# powerboost.net
KiCad netlist of a schematic drawn in EAGLE
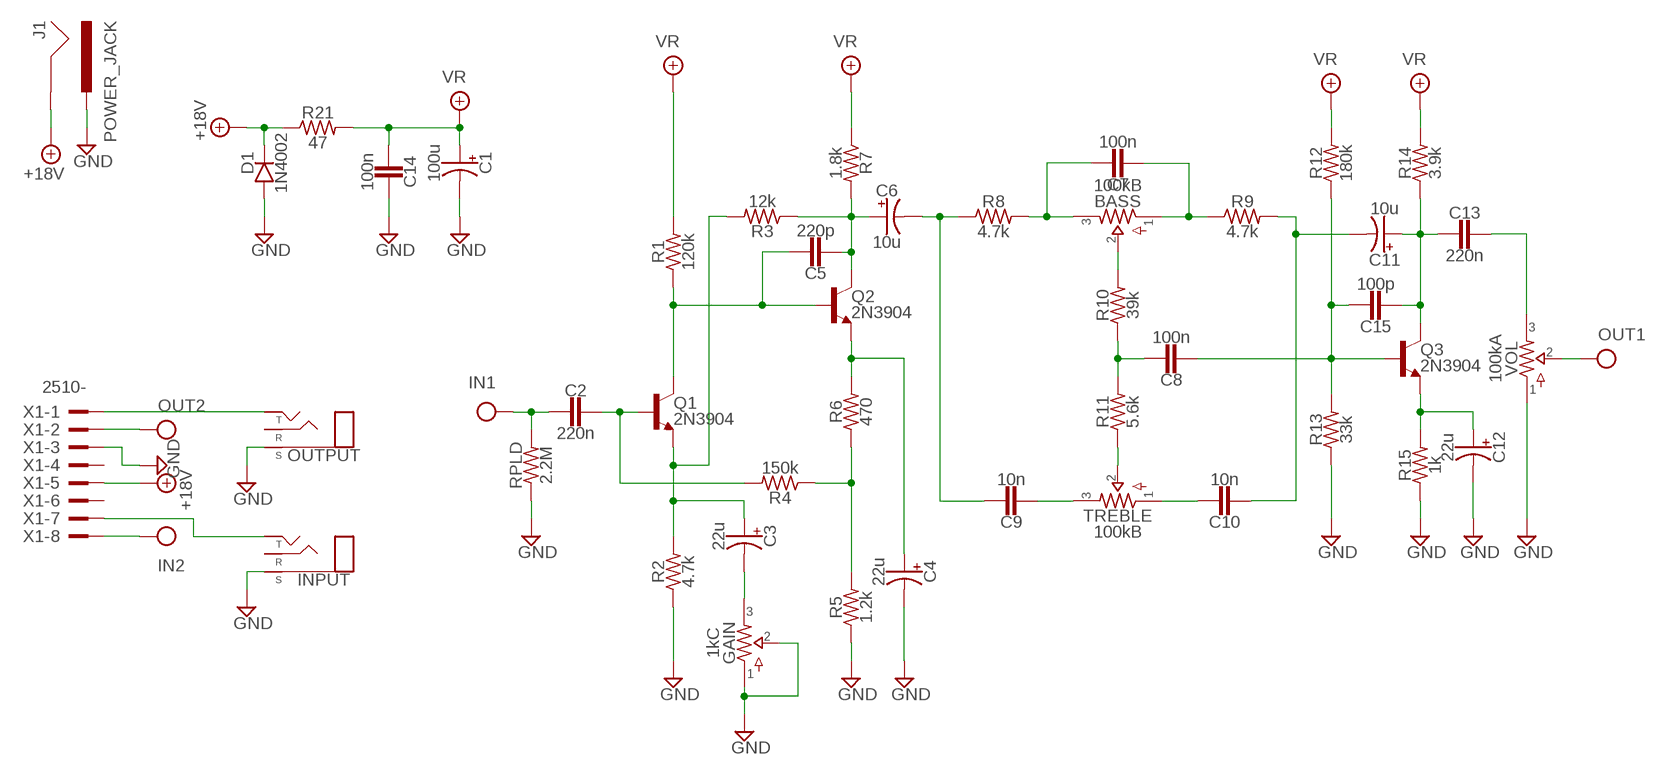
[diagram p0: schematic, sheet 1]

(export (version "E")
  (design (tool "Eeschema 10.0.6"))
  (components
    (comp (ref "BASS")
      (value "100kB")
      (footprint "eagle-import:16MM")
      (libsource (lib "eagle-import") (part "POTS16MM"))
    )
    (comp (ref "C1")
      (value "100u")
      (footprint "eagle-import:063_025")
      (libsource (lib "eagle-import") (part "0631"))
    )
    (comp (ref "C2")
      (value "220n")
      (footprint "eagle-import:BOX_SMALL")
      (libsource (lib "eagle-import") (part "CER/FILMBOX.1"))
    )
    (comp (ref "C3")
      (value "22u")
      (footprint "eagle-import:050_020")
      (libsource (lib "eagle-import") (part "0500"))
    )
    (comp (ref "C4")
      (value "22u")
      (footprint "eagle-import:050_020")
      (libsource (lib "eagle-import") (part "0500"))
    )
    (comp (ref "C5")
      (value "220p")
      (footprint "eagle-import:050X030_025_2")
      (libsource (lib "eagle-import") (part "CER/FILM2"))
    )
    (comp (ref "C6")
      (value "10u")
      (footprint "eagle-import:050_020_1")
      (libsource (lib "eagle-import") (part "0501"))
    )
    (comp (ref "C7")
      (value "100n")
      (footprint "eagle-import:BOX_SMALL")
      (libsource (lib "eagle-import") (part "CER/FILMBOX.1"))
    )
    (comp (ref "C8")
      (value "100n")
      (footprint "eagle-import:BOX_SMALL")
      (libsource (lib "eagle-import") (part "CER/FILMBOX.1"))
    )
    (comp (ref "C9")
      (value "10n")
      (footprint "eagle-import:BOX_SMALL")
      (libsource (lib "eagle-import") (part "CER/FILMBOX.1"))
    )
    (comp (ref "C10")
      (value "10n")
      (footprint "eagle-import:BOX_SMALL")
      (libsource (lib "eagle-import") (part "CER/FILMBOX.1"))
    )
    (comp (ref "C11")
      (value "10u")
      (footprint "eagle-import:050_020_1")
      (libsource (lib "eagle-import") (part "0501"))
    )
    (comp (ref "C12")
      (value "22u")
      (footprint "eagle-import:050_020")
      (libsource (lib "eagle-import") (part "0500"))
    )
    (comp (ref "C13")
      (value "220n")
      (footprint "eagle-import:BOX_SMALL")
      (libsource (lib "eagle-import") (part "CER/FILMBOX.1"))
    )
    (comp (ref "C14")
      (value "100n")
      (footprint "eagle-import:050X030_025_2")
      (libsource (lib "eagle-import") (part "CER/FILM2"))
    )
    (comp (ref "C15")
      (value "100p")
      (footprint "eagle-import:050X030_025_2")
      (libsource (lib "eagle-import") (part "CER/FILM2"))
    )
    (comp (ref "D1")
      (value "1N4002")
      (footprint "eagle-import:DO41-2")
      (libsource (lib "eagle-import") (part "DO41.2"))
    )
    (comp (ref "GAIN")
      (value "1kC")
      (footprint "eagle-import:16MM")
      (libsource (lib "eagle-import") (part "POTS16MM"))
    )
    (comp (ref "INPUT")
      (value "STEREONMJ")
      (footprint "eagle-import:NMJ6HCD2")
      (libsource (lib "eagle-import") (part "STEREONMJ"))
    )
    (comp (ref "J1")
      (value "POWER_JACK")
      (footprint "eagle-import:POWER_JACK_PTH")
      (libsource (lib "eagle-import") (part "POWER_JACK"))
    )
    (comp (ref "OUTPUT")
      (value "STEREONMJ")
      (footprint "eagle-import:NMJ6HCD2")
      (libsource (lib "eagle-import") (part "STEREONMJ"))
    )
    (comp (ref "Q1")
      (value "2N3904")
      (footprint "eagle-import:TO92-")
      (libsource (lib "eagle-import") (part "2N3904"))
    )
    (comp (ref "Q2")
      (value "2N3904")
      (footprint "eagle-import:TO92-")
      (libsource (lib "eagle-import") (part "2N3904"))
    )
    (comp (ref "Q3")
      (value "2N3904")
      (footprint "eagle-import:TO92-")
      (libsource (lib "eagle-import") (part "2N3904"))
    )
    (comp (ref "R1")
      (value "120k")
      (footprint "eagle-import:R0207_3")
      (libsource (lib "eagle-import") (part "R_.3B"))
    )
    (comp (ref "R2")
      (value "4.7k")
      (footprint "eagle-import:R0207_3")
      (libsource (lib "eagle-import") (part "R_.3B"))
    )
    (comp (ref "R3")
      (value "12k")
      (footprint "eagle-import:R0207_3")
      (libsource (lib "eagle-import") (part "R_.3B"))
    )
    (comp (ref "R4")
      (value "150k")
      (footprint "eagle-import:R0207_3")
      (libsource (lib "eagle-import") (part "R_.3B"))
    )
    (comp (ref "R5")
      (value "1.2k")
      (footprint "eagle-import:R0207_3")
      (libsource (lib "eagle-import") (part "R_.3B"))
    )
    (comp (ref "R6")
      (value "470")
      (footprint "eagle-import:R0207_3")
      (libsource (lib "eagle-import") (part "R_.3B"))
    )
    (comp (ref "R7")
      (value "1.8k")
      (footprint "eagle-import:R0207_3")
      (libsource (lib "eagle-import") (part "R_.3B"))
    )
    (comp (ref "R8")
      (value "4.7k")
      (footprint "eagle-import:R0207_3")
      (libsource (lib "eagle-import") (part "R_.3B"))
    )
    (comp (ref "R9")
      (value "4.7k")
      (footprint "eagle-import:R0207_3")
      (libsource (lib "eagle-import") (part "R_.3B"))
    )
    (comp (ref "R10")
      (value "39k")
      (footprint "eagle-import:R0207_3")
      (libsource (lib "eagle-import") (part "R_.3B"))
    )
    (comp (ref "R11")
      (value "5.6k")
      (footprint "eagle-import:R0207_3")
      (libsource (lib "eagle-import") (part "R_.3B"))
    )
    (comp (ref "R12")
      (value "180k")
      (footprint "eagle-import:R0207_3")
      (libsource (lib "eagle-import") (part "R_.3B"))
    )
    (comp (ref "R13")
      (value "33k")
      (footprint "eagle-import:R0207_3")
      (libsource (lib "eagle-import") (part "R_.3B"))
    )
    (comp (ref "R14")
      (value "3.9k")
      (footprint "eagle-import:R0207_3")
      (libsource (lib "eagle-import") (part "R_.3B"))
    )
    (comp (ref "R15")
      (value "1k")
      (footprint "eagle-import:R0207_3")
      (libsource (lib "eagle-import") (part "R_.3B"))
    )
    (comp (ref "R21")
      (value "47")
      (footprint "eagle-import:R0207_3")
      (libsource (lib "eagle-import") (part "R_.3B"))
    )
    (comp (ref "RPLD")
      (value "2.2M")
      (footprint "eagle-import:R0207_3")
      (libsource (lib "eagle-import") (part "R_.3B"))
    )
    (comp (ref "TREBLE")
      (value "100kB")
      (footprint "eagle-import:16MM")
      (libsource (lib "eagle-import") (part "POTS16MM"))
    )
    (comp (ref "VOL")
      (value "100kA")
      (footprint "eagle-import:16MM")
      (libsource (lib "eagle-import") (part "POTS16MM"))
    )
    (comp (ref "X1")
      (value "2510-")
      (footprint "eagle-import:PAK100_2500-10")
      (fields (field (name "MF") "3M") (field (name "MPN") "2510-6002UB"))
      (libsource (lib "eagle-import") (part "2510-"))
    )
  )
  (nets
    (net (code "1") (name "+18V") (class "Default")
      (node (ref "D1") (pin "C") (pinfunction "C_C") (pintype "passive"))
      (node (ref "J1") (pin "GND") (pinfunction "GND_GND") (pintype "bidirectional"))
      (node (ref "R21") (pin "1") (pinfunction "1_1") (pintype "passive"))
      (node (ref "X1") (pin "5") (pinfunction "KL_5") (pintype "passive"))
    )
    (net (code "2") (name "GND") (class "Default")
      (node (ref "C1") (pin "-") (pinfunction "-_-") (pintype "passive"))
      (node (ref "C12") (pin "-") (pinfunction "-_-") (pintype "passive"))
      (node (ref "C14") (pin "1") (pinfunction "1_1") (pintype "passive"))
      (node (ref "C4") (pin "-") (pinfunction "-_-") (pintype "passive"))
      (node (ref "D1") (pin "A") (pinfunction "A_A") (pintype "passive"))
      (node (ref "GAIN") (pin "1") (pinfunction "1_1") (pintype "passive"))
      (node (ref "GAIN") (pin "2") (pinfunction "2_2") (pintype "passive"))
      (node (ref "INPUT") (pin "S") (pinfunction "S_S") (pintype "passive"))
      (node (ref "J1") (pin "PWR") (pinfunction "PWR_PWR") (pintype "bidirectional"))
      (node (ref "OUTPUT") (pin "S") (pinfunction "S_S") (pintype "passive"))
      (node (ref "R13") (pin "1") (pinfunction "1_1") (pintype "passive"))
      (node (ref "R15") (pin "1") (pinfunction "1_1") (pintype "passive"))
      (node (ref "R2") (pin "1") (pinfunction "1_1") (pintype "passive"))
      (node (ref "R5") (pin "1") (pinfunction "1_1") (pintype "passive"))
      (node (ref "RPLD") (pin "1") (pinfunction "1_1") (pintype "passive"))
      (node (ref "VOL") (pin "1") (pinfunction "1_1") (pintype "passive"))
      (node (ref "X1") (pin "3") (pinfunction "KL_3") (pintype "passive"))
    )
    (net (code "3") (name "IN") (class "Default")
      (node (ref "C2") (pin "2") (pinfunction "2_2") (pintype "passive"))
      (node (ref "RPLD") (pin "2") (pinfunction "2_2") (pintype "passive"))
      (node (ref "X1") (pin "8") (pinfunction "KL_8") (pintype "passive"))
    )
    (net (code "4") (name "Net-(BASS-Pad1)") (class "Default")
      (node (ref "BASS") (pin "1") (pinfunction "1_1") (pintype "passive"))
      (node (ref "C7") (pin "2") (pinfunction "2_2") (pintype "passive"))
      (node (ref "R9") (pin "1") (pinfunction "1_1") (pintype "passive"))
    )
    (net (code "5") (name "Net-(BASS-Pad2)") (class "Default")
      (node (ref "BASS") (pin "2") (pinfunction "2_2") (pintype "passive"))
      (node (ref "R10") (pin "2") (pinfunction "2_2") (pintype "passive"))
    )
    (net (code "6") (name "Net-(BASS-Pad3)") (class "Default")
      (node (ref "BASS") (pin "3") (pinfunction "3_3") (pintype "passive"))
      (node (ref "C7") (pin "1") (pinfunction "1_1") (pintype "passive"))
      (node (ref "R8") (pin "2") (pinfunction "2_2") (pintype "passive"))
    )
    (net (code "7") (name "Net-(C3-Pad-)") (class "Default")
      (node (ref "C3") (pin "-") (pinfunction "-_-") (pintype "passive"))
      (node (ref "GAIN") (pin "3") (pinfunction "3_3") (pintype "passive"))
    )
    (net (code "8") (name "Net-(C6-Pad-)") (class "Default")
      (node (ref "C6") (pin "-") (pinfunction "-_-") (pintype "passive"))
      (node (ref "C9") (pin "1") (pinfunction "1_1") (pintype "passive"))
      (node (ref "R8") (pin "1") (pinfunction "1_1") (pintype "passive"))
    )
    (net (code "9") (name "Net-(C8-Pad1)") (class "Default")
      (node (ref "C8") (pin "1") (pinfunction "1_1") (pintype "passive"))
      (node (ref "R10") (pin "1") (pinfunction "1_1") (pintype "passive"))
      (node (ref "R11") (pin "2") (pinfunction "2_2") (pintype "passive"))
    )
    (net (code "10") (name "Net-(C9-Pad2)") (class "Default")
      (node (ref "C9") (pin "2") (pinfunction "2_2") (pintype "passive"))
      (node (ref "TREBLE") (pin "3") (pinfunction "3_3") (pintype "passive"))
    )
    (net (code "11") (name "Net-(C10-Pad1)") (class "Default")
      (node (ref "C10") (pin "1") (pinfunction "1_1") (pintype "passive"))
      (node (ref "TREBLE") (pin "1") (pinfunction "1_1") (pintype "passive"))
    )
    (net (code "12") (name "Net-(C10-Pad2)") (class "Default")
      (node (ref "C10") (pin "2") (pinfunction "2_2") (pintype "passive"))
      (node (ref "C11") (pin "-") (pinfunction "-_-") (pintype "passive"))
      (node (ref "R9") (pin "2") (pinfunction "2_2") (pintype "passive"))
    )
    (net (code "13") (name "Net-(C13-Pad1)") (class "Default")
      (node (ref "C13") (pin "1") (pinfunction "1_1") (pintype "passive"))
      (node (ref "VOL") (pin "3") (pinfunction "3_3") (pintype "passive"))
    )
    (net (code "14") (name "Net-(Q1-B)") (class "Default")
      (node (ref "C2") (pin "1") (pinfunction "1_1") (pintype "passive"))
      (node (ref "Q1") (pin "2") (pinfunction "B_2") (pintype "passive"))
      (node (ref "R4") (pin "2") (pinfunction "2_2") (pintype "passive"))
    )
    (net (code "15") (name "Net-(Q1-C)") (class "Default")
      (node (ref "C5") (pin "1") (pinfunction "1_1") (pintype "passive"))
      (node (ref "Q1") (pin "1") (pinfunction "C_1") (pintype "passive"))
      (node (ref "Q2") (pin "2") (pinfunction "B_2") (pintype "passive"))
      (node (ref "R1") (pin "1") (pinfunction "1_1") (pintype "passive"))
    )
    (net (code "16") (name "Net-(Q1-E)") (class "Default")
      (node (ref "C3") (pin "+") (pinfunction "+_+") (pintype "passive"))
      (node (ref "Q1") (pin "3") (pinfunction "E_3") (pintype "passive"))
      (node (ref "R2") (pin "2") (pinfunction "2_2") (pintype "passive"))
      (node (ref "R3") (pin "2") (pinfunction "2_2") (pintype "passive"))
    )
    (net (code "17") (name "Net-(Q2-C)") (class "Default")
      (node (ref "C5") (pin "2") (pinfunction "2_2") (pintype "passive"))
      (node (ref "C6") (pin "+") (pinfunction "+_+") (pintype "passive"))
      (node (ref "Q2") (pin "1") (pinfunction "C_1") (pintype "passive"))
      (node (ref "R3") (pin "1") (pinfunction "1_1") (pintype "passive"))
      (node (ref "R7") (pin "2") (pinfunction "2_2") (pintype "passive"))
    )
    (net (code "18") (name "Net-(Q2-E)") (class "Default")
      (node (ref "C4") (pin "+") (pinfunction "+_+") (pintype "passive"))
      (node (ref "Q2") (pin "3") (pinfunction "E_3") (pintype "passive"))
      (node (ref "R6") (pin "2") (pinfunction "2_2") (pintype "passive"))
    )
    (net (code "19") (name "Net-(Q3-B)") (class "Default")
      (node (ref "C15") (pin "1") (pinfunction "1_1") (pintype "passive"))
      (node (ref "C8") (pin "2") (pinfunction "2_2") (pintype "passive"))
      (node (ref "Q3") (pin "2") (pinfunction "B_2") (pintype "passive"))
      (node (ref "R12") (pin "1") (pinfunction "1_1") (pintype "passive"))
      (node (ref "R13") (pin "2") (pinfunction "2_2") (pintype "passive"))
    )
    (net (code "20") (name "Net-(Q3-C)") (class "Default")
      (node (ref "C11") (pin "+") (pinfunction "+_+") (pintype "passive"))
      (node (ref "C13") (pin "2") (pinfunction "2_2") (pintype "passive"))
      (node (ref "C15") (pin "2") (pinfunction "2_2") (pintype "passive"))
      (node (ref "Q3") (pin "1") (pinfunction "C_1") (pintype "passive"))
      (node (ref "R14") (pin "1") (pinfunction "1_1") (pintype "passive"))
    )
    (net (code "21") (name "Net-(Q3-E)") (class "Default")
      (node (ref "C12") (pin "+") (pinfunction "+_+") (pintype "passive"))
      (node (ref "Q3") (pin "3") (pinfunction "E_3") (pintype "passive"))
      (node (ref "R15") (pin "2") (pinfunction "2_2") (pintype "passive"))
    )
    (net (code "22") (name "Net-(R4-Pad1)") (class "Default")
      (node (ref "R4") (pin "1") (pinfunction "1_1") (pintype "passive"))
      (node (ref "R5") (pin "2") (pinfunction "2_2") (pintype "passive"))
      (node (ref "R6") (pin "1") (pinfunction "1_1") (pintype "passive"))
    )
    (net (code "23") (name "Net-(R11-Pad1)") (class "Default")
      (node (ref "R11") (pin "1") (pinfunction "1_1") (pintype "passive"))
      (node (ref "TREBLE") (pin "2") (pinfunction "2_2") (pintype "passive"))
    )
    (net (code "24") (name "Net-(X1A-KL)") (class "Default")
      (node (ref "OUTPUT") (pin "T") (pinfunction "T_T") (pintype "passive"))
      (node (ref "X1") (pin "1") (pinfunction "KL_1") (pintype "passive"))
    )
    (net (code "25") (name "Net-(X1G-KL)") (class "Default")
      (node (ref "INPUT") (pin "T") (pinfunction "T_T") (pintype "passive"))
      (node (ref "X1") (pin "7") (pinfunction "KL_7") (pintype "passive"))
    )
    (net (code "26") (name "OUT") (class "Default")
      (node (ref "VOL") (pin "2") (pinfunction "2_2") (pintype "passive"))
      (node (ref "X1") (pin "2") (pinfunction "KL_2") (pintype "passive"))
    )
    (net (code "27") (name "VR") (class "Default")
      (node (ref "C1") (pin "+") (pinfunction "+_+") (pintype "passive"))
      (node (ref "C14") (pin "2") (pinfunction "2_2") (pintype "passive"))
      (node (ref "R1") (pin "2") (pinfunction "2_2") (pintype "passive"))
      (node (ref "R12") (pin "2") (pinfunction "2_2") (pintype "passive"))
      (node (ref "R14") (pin "2") (pinfunction "2_2") (pintype "passive"))
      (node (ref "R21") (pin "2") (pinfunction "2_2") (pintype "passive"))
      (node (ref "R7") (pin "1") (pinfunction "1_1") (pintype "passive"))
    )
    (net (code "28") (name "unconnected-(INPUT-PadR)") (class "Default")
      (node (ref "INPUT") (pin "R") (pinfunction "R_R") (pintype "passive"))
    )
    (net (code "29") (name "unconnected-(OUTPUT-PadR)") (class "Default")
      (node (ref "OUTPUT") (pin "R") (pinfunction "R_R") (pintype "passive"))
    )
    (net (code "30") (name "unconnected-(X1D-KL-Pad4)") (class "Default")
      (node (ref "X1") (pin "4") (pinfunction "KL_4") (pintype "passive"))
    )
    (net (code "31") (name "unconnected-(X1F-KL-Pad6)") (class "Default")
      (node (ref "X1") (pin "6") (pinfunction "KL_6") (pintype "passive"))
    )
  )
)
